# laser_show_core.net
KiCad netlist of a schematic drawn in Altium Designer
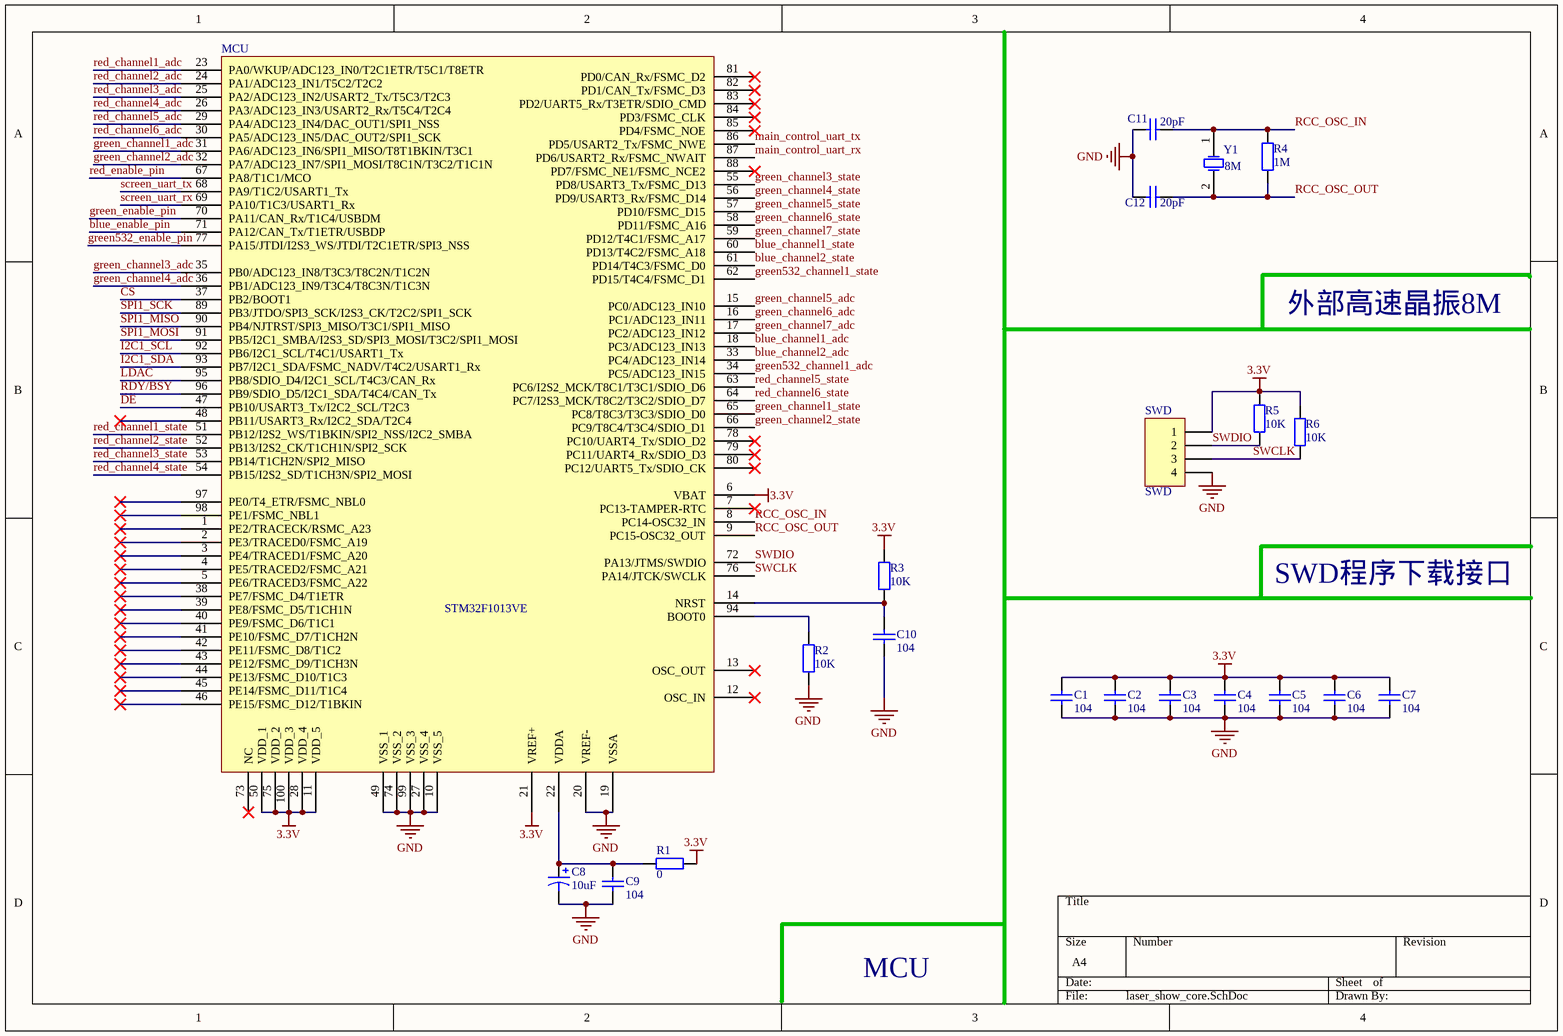
[diagram p0: laser_show_core.SchDoc]

(export (version "E")
  (design (tool "Eeschema 10.0.6"))
  (components
    (comp (ref "C1")
      (value "104")
      (footprint "0603C")
      (description "capacitance")
      (libsource (lib "RobotSCHLibrary") (part "CAP"))
    )
    (comp (ref "C2")
      (value "104")
      (footprint "0603C")
      (description "capacitance")
      (libsource (lib "RobotSCHLibrary") (part "CAP"))
    )
    (comp (ref "C3")
      (value "104")
      (footprint "0603C")
      (description "capacitance")
      (libsource (lib "RobotSCHLibrary") (part "CAP"))
    )
    (comp (ref "C4")
      (value "104")
      (footprint "0603C")
      (description "capacitance")
      (libsource (lib "RobotSCHLibrary") (part "CAP"))
    )
    (comp (ref "C5")
      (value "104")
      (footprint "0603C")
      (description "capacitance")
      (libsource (lib "RobotSCHLibrary") (part "CAP"))
    )
    (comp (ref "C6")
      (value "104")
      (footprint "0603C")
      (description "capacitance")
      (libsource (lib "RobotSCHLibrary") (part "CAP"))
    )
    (comp (ref "C7")
      (value "104")
      (footprint "0603C")
      (description "capacitance")
      (libsource (lib "RobotSCHLibrary") (part "CAP"))
    )
    (comp (ref "C8")
      (value "10uF")
      (footprint "0805CAP_POL")
      (description "Cap polar")
      (libsource (lib "RobotSCHLibrary") (part "CAP_Polar"))
    )
    (comp (ref "C9")
      (value "104")
      (footprint "0805C")
      (description "capacitance")
      (libsource (lib "RobotSCHLibrary") (part "CAP"))
    )
    (comp (ref "C10")
      (value "104")
      (footprint "0805C")
      (description "capacitance")
      (libsource (lib "RobotSCHLibrary") (part "CAP"))
    )
    (comp (ref "C11")
      (value "20pF")
      (footprint "0805C")
      (description "capacitance")
      (libsource (lib "RobotSCHLibrary") (part "CAP"))
    )
    (comp (ref "C12")
      (value "20pF")
      (footprint "0805C")
      (description "capacitance")
      (libsource (lib "RobotSCHLibrary") (part "CAP"))
    )
    (comp (ref "MCU")
      (value "STM32F1013VE")
      (footprint "LQFP100_L")
      (description "STM32F1013VET6")
      (libsource (lib "RobotSCHLibrary") (part "STM32F103VET6"))
    )
    (comp (ref "R1")
      (value "0")
      (footprint "0603R")
      (description "resistor")
      (libsource (lib "") (part "RES_2"))
    )
    (comp (ref "R2")
      (value "10K")
      (footprint "0603R")
      (description "resistor")
      (libsource (lib "RobotSCHLibrary") (part "RES"))
    )
    (comp (ref "R3")
      (value "10K")
      (footprint "0805R")
      (description "resistor")
      (libsource (lib "RobotSCHLibrary") (part "RES"))
    )
    (comp (ref "R4")
      (value "1M")
      (footprint "0805R")
      (description "resistor")
      (libsource (lib "") (part "RES_1"))
    )
    (comp (ref "R5")
      (value "10K")
      (footprint "0805R")
      (description "resistor")
      (libsource (lib "RobotSCHLibrary") (part "RES"))
    )
    (comp (ref "R6")
      (value "10K")
      (footprint "0805R")
      (description "resistor")
      (libsource (lib "RobotSCHLibrary") (part "RES"))
    )
    (comp (ref "SWD")
      (value "SWD")
      (footprint "HDR1X4")
      (description "Header, 4-Pin")
      (fields (field (name "PUBLISHER") "Altium Limited"))
      (libsource (lib "Miscellaneous Connectors") (part "Header 4"))
    )
    (comp (ref "Y1")
      (value "8M")
      (footprint "XTAL1")
      (description "crystal")
      (libsource (lib "RobotSCHLibrary") (part "8M"))
    )
  )
  (nets
    (net (code "1") (name "/CS") (class "Default")
      (node (ref "MCU") (pin "37") (pinfunction "PB2/BOOT1_37") (pintype "passive"))
    )
    (net (code "2") (name "/DE") (class "Default")
      (node (ref "MCU") (pin "47") (pinfunction "PB10/USART3_Tx/I2C2_SCL/T2C3_47") (pintype "passive"))
    )
    (net (code "3") (name "/I2C1_SCL") (class "Default")
      (node (ref "MCU") (pin "92") (pinfunction "PB6/I2C1_SCL/T4C1/USART1_Tx_92") (pintype "passive"))
    )
    (net (code "4") (name "/I2C1_SDA") (class "Default")
      (node (ref "MCU") (pin "93") (pinfunction "PB7/I2C1_SDA/FSMC_NADV/T4C2/USART1_Rx_93") (pintype "passive"))
    )
    (net (code "5") (name "/RCC_OSC_IN") (class "Default")
      (node (ref "C11") (pin "1") (pinfunction "1_1") (pintype "passive"))
      (node (ref "MCU") (pin "8") (pinfunction "PC14-OSC32_IN_8") (pintype "passive"))
      (node (ref "R4") (pin "1") (pinfunction "1_1") (pintype "passive"))
      (node (ref "Y1") (pin "1") (pinfunction "OSC1_1") (pintype "passive"))
    )
    (net (code "6") (name "/RCC_OSC_OUT") (class "Default")
      (node (ref "C12") (pin "1") (pinfunction "1_1") (pintype "passive"))
      (node (ref "MCU") (pin "9") (pinfunction "PC15-OSC32_OUT_9") (pintype "passive"))
      (node (ref "R4") (pin "2") (pinfunction "2_2") (pintype "passive"))
      (node (ref "Y1") (pin "2") (pinfunction "OSC2_2") (pintype "passive"))
    )
    (net (code "7") (name "/RDY{slash}~{BSY}") (class "Default")
      (node (ref "MCU") (pin "96") (pinfunction "PB9/SDIO_D5/I2C1_SDA/T4C4/CAN_Tx_96") (pintype "passive"))
    )
    (net (code "8") (name "/SPI1_MISO") (class "Default")
      (node (ref "MCU") (pin "90") (pinfunction "PB4/NJTRST/SPI3_MISO/T3C1/SPI1_MISO_90") (pintype "passive"))
    )
    (net (code "9") (name "/SPI1_MOSI") (class "Default")
      (node (ref "MCU") (pin "91") (pinfunction "PB5/I2C1_SMBA/I2S3_SD/SPI3_MOSI/T3C2/SPI1_MOSI_91") (pintype "passive"))
    )
    (net (code "10") (name "/SPI1_SCK") (class "Default")
      (node (ref "MCU") (pin "89") (pinfunction "PB3/JTDO/SPI3_SCK/I2S3_CK/T2C2/SPI1_SCK_89") (pintype "passive"))
    )
    (net (code "11") (name "/SWCLK") (class "Default")
      (node (ref "MCU") (pin "76") (pinfunction "PA14/JTCK/SWCLK_76") (pintype "passive"))
      (node (ref "R6") (pin "1") (pinfunction "1_1") (pintype "passive"))
      (node (ref "SWD") (pin "3") (pinfunction "3_3") (pintype "passive"))
    )
    (net (code "12") (name "/SWDIO") (class "Default")
      (node (ref "MCU") (pin "72") (pinfunction "PA13/JTMS/SWDIO_72") (pintype "passive"))
      (node (ref "R5") (pin "1") (pinfunction "1_1") (pintype "passive"))
      (node (ref "SWD") (pin "2") (pinfunction "2_2") (pintype "passive"))
    )
    (net (code "13") (name "/blue_channel1_adc") (class "Default")
      (node (ref "MCU") (pin "18") (pinfunction "PC3/ADC123_IN13_18") (pintype "passive"))
    )
    (net (code "14") (name "/blue_channel1_state") (class "Default")
      (node (ref "MCU") (pin "60") (pinfunction "PD13/T4C2/FSMC_A18_60") (pintype "passive"))
    )
    (net (code "15") (name "/blue_channel2_adc") (class "Default")
      (node (ref "MCU") (pin "33") (pinfunction "PC4/ADC123_IN14_33") (pintype "passive"))
    )
    (net (code "16") (name "/blue_channel2_state") (class "Default")
      (node (ref "MCU") (pin "61") (pinfunction "PD14/T4C3/FSMC_D0_61") (pintype "passive"))
    )
    (net (code "17") (name "/blue_enable_pin") (class "Default")
      (node (ref "MCU") (pin "71") (pinfunction "PA12/CAN_Tx/T1ETR/USBDP_71") (pintype "passive"))
    )
    (net (code "18") (name "/green532_channel1_adc") (class "Default")
      (node (ref "MCU") (pin "34") (pinfunction "PC5/ADC123_IN15_34") (pintype "passive"))
    )
    (net (code "19") (name "/green532_channel1_state") (class "Default")
      (node (ref "MCU") (pin "62") (pinfunction "PD15/T4C4/FSMC_D1_62") (pintype "passive"))
    )
    (net (code "20") (name "/green532_enable_pin") (class "Default")
      (node (ref "MCU") (pin "77") (pinfunction "PA15/JTDI/I2S3_WS/JTDI/T2C1ETR/SPI3_NSS_77") (pintype "passive"))
    )
    (net (code "21") (name "/green_channel1_adc") (class "Default")
      (node (ref "MCU") (pin "31") (pinfunction "PA6/ADC123_IN6/SPI1_MISO/T8T1BKIN/T3C1_31") (pintype "passive"))
    )
    (net (code "22") (name "/green_channel1_state") (class "Default")
      (node (ref "MCU") (pin "65") (pinfunction "PC8/T8C3/T3C3/SDIO_D0_65") (pintype "passive"))
    )
    (net (code "23") (name "/green_channel2_adc") (class "Default")
      (node (ref "MCU") (pin "32") (pinfunction "PA7/ADC123_IN7/SPI1_MOSI/T8C1N/T3C2/T1C1N_32") (pintype "passive"))
    )
    (net (code "24") (name "/green_channel2_state") (class "Default")
      (node (ref "MCU") (pin "66") (pinfunction "PC9/T8C4/T3C4/SDIO_D1_66") (pintype "passive"))
    )
    (net (code "25") (name "/green_channel3_adc") (class "Default")
      (node (ref "MCU") (pin "35") (pinfunction "PB0/ADC123_IN8/T3C3/T8C2N/T1C2N_35") (pintype "passive"))
    )
    (net (code "26") (name "/green_channel3_state") (class "Default")
      (node (ref "MCU") (pin "55") (pinfunction "PD8/USART3_Tx/FSMC_D13_55") (pintype "passive"))
    )
    (net (code "27") (name "/green_channel4_adc") (class "Default")
      (node (ref "MCU") (pin "36") (pinfunction "PB1/ADC123_IN9/T3C4/T8C3N/T1C3N_36") (pintype "passive"))
    )
    (net (code "28") (name "/green_channel4_state") (class "Default")
      (node (ref "MCU") (pin "56") (pinfunction "PD9/USART3_Rx/FSMC_D14_56") (pintype "passive"))
    )
    (net (code "29") (name "/green_channel5_adc") (class "Default")
      (node (ref "MCU") (pin "15") (pinfunction "PC0/ADC123_IN10_15") (pintype "passive"))
    )
    (net (code "30") (name "/green_channel5_state") (class "Default")
      (node (ref "MCU") (pin "57") (pinfunction "PD10/FSMC_D15_57") (pintype "passive"))
    )
    (net (code "31") (name "/green_channel6_adc") (class "Default")
      (node (ref "MCU") (pin "16") (pinfunction "PC1/ADC123_IN11_16") (pintype "passive"))
    )
    (net (code "32") (name "/green_channel6_state") (class "Default")
      (node (ref "MCU") (pin "58") (pinfunction "PD11/FSMC_A16_58") (pintype "passive"))
    )
    (net (code "33") (name "/green_channel7_adc") (class "Default")
      (node (ref "MCU") (pin "17") (pinfunction "PC2/ADC123_IN12_17") (pintype "passive"))
    )
    (net (code "34") (name "/green_channel7_state") (class "Default")
      (node (ref "MCU") (pin "59") (pinfunction "PD12/T4C1/FSMC_A17_59") (pintype "passive"))
    )
    (net (code "35") (name "/green_enable_pin") (class "Default")
      (node (ref "MCU") (pin "70") (pinfunction "PA11/CAN_Rx/T1C4/USBDM_70") (pintype "passive"))
    )
    (net (code "36") (name "/main_control_uart_rx") (class "Default")
      (node (ref "MCU") (pin "87") (pinfunction "PD6/USART2_Rx/FSMC_NWAIT_87") (pintype "passive"))
    )
    (net (code "37") (name "/main_control_uart_tx") (class "Default")
      (node (ref "MCU") (pin "86") (pinfunction "PD5/USART2_Tx/FSMC_NWE_86") (pintype "passive"))
    )
    (net (code "38") (name "/red_channel1_adc") (class "Default")
      (node (ref "MCU") (pin "23") (pinfunction "PA0/WKUP/ADC123_IN0/T2C1ETR/T5C1/T8ETR_23") (pintype "passive"))
    )
    (net (code "39") (name "/red_channel1_state") (class "Default")
      (node (ref "MCU") (pin "51") (pinfunction "PB12/I2S2_WS/T1BKIN/SPI2_NSS/I2C2_SMBA_51") (pintype "passive"))
    )
    (net (code "40") (name "/red_channel2_adc") (class "Default")
      (node (ref "MCU") (pin "24") (pinfunction "PA1/ADC123_IN1/T5C2/T2C2_24") (pintype "passive"))
    )
    (net (code "41") (name "/red_channel2_state") (class "Default")
      (node (ref "MCU") (pin "52") (pinfunction "PB13/I2S2_CK/T1CH1N/SPI2_SCK_52") (pintype "passive"))
    )
    (net (code "42") (name "/red_channel3_adc") (class "Default")
      (node (ref "MCU") (pin "25") (pinfunction "PA2/ADC123_IN2/USART2_Tx/T5C3/T2C3_25") (pintype "passive"))
    )
    (net (code "43") (name "/red_channel3_state") (class "Default")
      (node (ref "MCU") (pin "53") (pinfunction "PB14/T1CH2N/SPI2_MISO_53") (pintype "passive"))
    )
    (net (code "44") (name "/red_channel4_adc") (class "Default")
      (node (ref "MCU") (pin "26") (pinfunction "PA3/ADC123_IN3/USART2_Rx/T5C4/T2C4_26") (pintype "passive"))
    )
    (net (code "45") (name "/red_channel4_state") (class "Default")
      (node (ref "MCU") (pin "54") (pinfunction "PB15/I2S2_SD/T1CH3N/SPI2_MOSI_54") (pintype "passive"))
    )
    (net (code "46") (name "/red_channel5_adc") (class "Default")
      (node (ref "MCU") (pin "29") (pinfunction "PA4/ADC123_IN4/DAC_OUT1/SPI1_NSS_29") (pintype "passive"))
    )
    (net (code "47") (name "/red_channel5_state") (class "Default")
      (node (ref "MCU") (pin "63") (pinfunction "PC6/I2S2_MCK/T8C1/T3C1/SDIO_D6_63") (pintype "passive"))
    )
    (net (code "48") (name "/red_channel6_adc") (class "Default")
      (node (ref "MCU") (pin "30") (pinfunction "PA5/ADC123_IN5/DAC_OUT2/SPI1_SCK_30") (pintype "passive"))
    )
    (net (code "49") (name "/red_channel6_state") (class "Default")
      (node (ref "MCU") (pin "64") (pinfunction "PC7/I2S3_MCK/T8C2/T3C2/SDIO_D7_64") (pintype "passive"))
    )
    (net (code "50") (name "/red_enable_pin") (class "Default")
      (node (ref "MCU") (pin "67") (pinfunction "PA8/T1C1/MCO_67") (pintype "passive"))
    )
    (net (code "51") (name "/screen_uart_rx") (class "Default")
      (node (ref "MCU") (pin "69") (pinfunction "PA10/T1C3/USART1_Rx_69") (pintype "passive"))
    )
    (net (code "52") (name "/screen_uart_tx") (class "Default")
      (node (ref "MCU") (pin "68") (pinfunction "PA9/T1C2/USART1_Tx_68") (pintype "passive"))
    )
    (net (code "53") (name "/~{LDA}C") (class "Default")
      (node (ref "MCU") (pin "95") (pinfunction "PB8/SDIO_D4/I2C1_SCL/T4C3/CAN_Rx_95") (pintype "passive"))
    )
    (net (code "54") (name "3.3V") (class "Default")
      (node (ref "C1") (pin "2") (pinfunction "2_2") (pintype "passive"))
      (node (ref "C2") (pin "2") (pinfunction "2_2") (pintype "passive"))
      (node (ref "C3") (pin "2") (pinfunction "2_2") (pintype "passive"))
      (node (ref "C4") (pin "2") (pinfunction "2_2") (pintype "passive"))
      (node (ref "C5") (pin "2") (pinfunction "2_2") (pintype "passive"))
      (node (ref "C6") (pin "2") (pinfunction "2_2") (pintype "passive"))
      (node (ref "C7") (pin "2") (pinfunction "2_2") (pintype "passive"))
      (node (ref "MCU") (pin "100") (pinfunction "VDD_3_100") (pintype "passive"))
      (node (ref "MCU") (pin "11") (pinfunction "VDD_5_11") (pintype "passive"))
      (node (ref "MCU") (pin "21") (pinfunction "VREF+_21") (pintype "passive"))
      (node (ref "MCU") (pin "28") (pinfunction "VDD_4_28") (pintype "passive"))
      (node (ref "MCU") (pin "50") (pinfunction "VDD_1_50") (pintype "passive"))
      (node (ref "MCU") (pin "6") (pinfunction "VBAT_6") (pintype "passive"))
      (node (ref "MCU") (pin "75") (pinfunction "VDD_2_75") (pintype "passive"))
      (node (ref "R1") (pin "2") (pinfunction "2_2") (pintype "passive"))
      (node (ref "R3") (pin "2") (pinfunction "2_2") (pintype "passive"))
      (node (ref "R5") (pin "2") (pinfunction "2_2") (pintype "passive"))
      (node (ref "R6") (pin "2") (pinfunction "2_2") (pintype "passive"))
      (node (ref "SWD") (pin "1") (pinfunction "1_1") (pintype "passive"))
    )
    (net (code "55") (name "GND") (class "Default")
      (node (ref "C1") (pin "1") (pinfunction "1_1") (pintype "passive"))
      (node (ref "C10") (pin "1") (pinfunction "1_1") (pintype "passive"))
      (node (ref "C11") (pin "2") (pinfunction "2_2") (pintype "passive"))
      (node (ref "C12") (pin "2") (pinfunction "2_2") (pintype "passive"))
      (node (ref "C2") (pin "1") (pinfunction "1_1") (pintype "passive"))
      (node (ref "C3") (pin "1") (pinfunction "1_1") (pintype "passive"))
      (node (ref "C4") (pin "1") (pinfunction "1_1") (pintype "passive"))
      (node (ref "C5") (pin "1") (pinfunction "1_1") (pintype "passive"))
      (node (ref "C6") (pin "1") (pinfunction "1_1") (pintype "passive"))
      (node (ref "C7") (pin "1") (pinfunction "1_1") (pintype "passive"))
      (node (ref "C8") (pin "2") (pinfunction "2_2") (pintype "passive"))
      (node (ref "C9") (pin "1") (pinfunction "1_1") (pintype "passive"))
      (node (ref "MCU") (pin "10") (pinfunction "VSS_5_10") (pintype "passive"))
      (node (ref "MCU") (pin "19") (pinfunction "VSSA_19") (pintype "passive"))
      (node (ref "MCU") (pin "20") (pinfunction "VREF-_20") (pintype "passive"))
      (node (ref "MCU") (pin "27") (pinfunction "VSS_4_27") (pintype "passive"))
      (node (ref "MCU") (pin "49") (pinfunction "VSS_1_49") (pintype "passive"))
      (node (ref "MCU") (pin "74") (pinfunction "VSS_2_74") (pintype "passive"))
      (node (ref "MCU") (pin "99") (pinfunction "VSS_3_99") (pintype "passive"))
      (node (ref "R2") (pin "1") (pinfunction "1_1") (pintype "passive"))
      (node (ref "SWD") (pin "4") (pinfunction "4_4") (pintype "passive"))
    )
    (net (code "56") (name "Net-(MCU-BOOT0)") (class "Default")
      (node (ref "MCU") (pin "94") (pinfunction "BOOT0_94") (pintype "passive"))
      (node (ref "R2") (pin "2") (pinfunction "2_2") (pintype "passive"))
    )
    (net (code "57") (name "Net-(MCU-NRST)") (class "Default")
      (node (ref "C10") (pin "2") (pinfunction "2_2") (pintype "passive"))
      (node (ref "MCU") (pin "14") (pinfunction "NRST_14") (pintype "passive"))
      (node (ref "R3") (pin "1") (pinfunction "1_1") (pintype "passive"))
    )
    (net (code "58") (name "Net-(MCU-VDDA)") (class "Default")
      (node (ref "C8") (pin "1") (pinfunction "1_1") (pintype "passive"))
      (node (ref "C9") (pin "2") (pinfunction "2_2") (pintype "passive"))
      (node (ref "MCU") (pin "22") (pinfunction "VDDA_22") (pintype "passive"))
      (node (ref "R1") (pin "1") (pinfunction "1_1") (pintype "passive"))
    )
    (net (code "59") (name "unconnected-(MCU-NC-Pad73)") (class "Default")
      (node (ref "MCU") (pin "73") (pinfunction "NC_73") (pintype "passive+no_connect"))
    )
    (net (code "60") (name "unconnected-(MCU-OSC_IN-Pad12)") (class "Default")
      (node (ref "MCU") (pin "12") (pinfunction "OSC_IN_12") (pintype "passive+no_connect"))
    )
    (net (code "61") (name "unconnected-(MCU-OSC_OUT-Pad13)") (class "Default")
      (node (ref "MCU") (pin "13") (pinfunction "OSC_OUT_13") (pintype "passive+no_connect"))
    )
    (net (code "62") (name "unconnected-(MCU-PB11{slash}USART3_Rx{slash}I2C2_SDA{slash}T2C4-Pad48)") (class "Default")
      (node (ref "MCU") (pin "48") (pinfunction "PB11/USART3_Rx/I2C2_SDA/T2C4_48") (pintype "passive+no_connect"))
    )
    (net (code "63") (name "unconnected-(MCU-PC10{slash}UART4_Tx{slash}SDIO_D2-Pad78)") (class "Default")
      (node (ref "MCU") (pin "78") (pinfunction "PC10/UART4_Tx/SDIO_D2_78") (pintype "passive+no_connect"))
    )
    (net (code "64") (name "unconnected-(MCU-PC11{slash}UART4_Rx{slash}SDIO_D3-Pad79)") (class "Default")
      (node (ref "MCU") (pin "79") (pinfunction "PC11/UART4_Rx/SDIO_D3_79") (pintype "passive+no_connect"))
    )
    (net (code "65") (name "unconnected-(MCU-PC12{slash}UART5_Tx{slash}SDIO_CK-Pad80)") (class "Default")
      (node (ref "MCU") (pin "80") (pinfunction "PC12/UART5_Tx/SDIO_CK_80") (pintype "passive+no_connect"))
    )
    (net (code "66") (name "unconnected-(MCU-PC13-TAMPER-RTC-Pad7)") (class "Default")
      (node (ref "MCU") (pin "7") (pinfunction "PC13-TAMPER-RTC_7") (pintype "passive+no_connect"))
    )
    (net (code "67") (name "unconnected-(MCU-PD0{slash}CAN_Rx{slash}FSMC_D2-Pad81)") (class "Default")
      (node (ref "MCU") (pin "81") (pinfunction "PD0/CAN_Rx/FSMC_D2_81") (pintype "passive+no_connect"))
    )
    (net (code "68") (name "unconnected-(MCU-PD1{slash}CAN_Tx{slash}FSMC_D3-Pad82)") (class "Default")
      (node (ref "MCU") (pin "82") (pinfunction "PD1/CAN_Tx/FSMC_D3_82") (pintype "passive+no_connect"))
    )
    (net (code "69") (name "unconnected-(MCU-PD2{slash}UART5_Rx{slash}T3ETR{slash}SDIO_CMD-Pad83)") (class "Default")
      (node (ref "MCU") (pin "83") (pinfunction "PD2/UART5_Rx/T3ETR/SDIO_CMD_83") (pintype "passive+no_connect"))
    )
    (net (code "70") (name "unconnected-(MCU-PD3{slash}FSMC_CLK-Pad84)") (class "Default")
      (node (ref "MCU") (pin "84") (pinfunction "PD3/FSMC_CLK_84") (pintype "passive+no_connect"))
    )
    (net (code "71") (name "unconnected-(MCU-PD4{slash}FSMC_NOE-Pad85)") (class "Default")
      (node (ref "MCU") (pin "85") (pinfunction "PD4/FSMC_NOE_85") (pintype "passive+no_connect"))
    )
    (net (code "72") (name "unconnected-(MCU-PD7{slash}FSMC_NE1{slash}FSMC_NCE2-Pad88)") (class "Default")
      (node (ref "MCU") (pin "88") (pinfunction "PD7/FSMC_NE1/FSMC_NCE2_88") (pintype "passive+no_connect"))
    )
    (net (code "73") (name "unconnected-(MCU-PE0{slash}T4_ETR{slash}FSMC_NBL0-Pad97)") (class "Default")
      (node (ref "MCU") (pin "97") (pinfunction "PE0/T4_ETR/FSMC_NBL0_97") (pintype "passive+no_connect"))
    )
    (net (code "74") (name "unconnected-(MCU-PE1{slash}FSMC_NBL1-Pad98)") (class "Default")
      (node (ref "MCU") (pin "98") (pinfunction "PE1/FSMC_NBL1_98") (pintype "passive+no_connect"))
    )
    (net (code "75") (name "unconnected-(MCU-PE2{slash}TRACECK{slash}RSMC_A23-Pad1)") (class "Default")
      (node (ref "MCU") (pin "1") (pinfunction "PE2/TRACECK/RSMC_A23_1") (pintype "passive+no_connect"))
    )
    (net (code "76") (name "unconnected-(MCU-PE3{slash}TRACED0{slash}FSMC_A19-Pad2)") (class "Default")
      (node (ref "MCU") (pin "2") (pinfunction "PE3/TRACED0/FSMC_A19_2") (pintype "passive+no_connect"))
    )
    (net (code "77") (name "unconnected-(MCU-PE4{slash}TRACED1{slash}FSMC_A20-Pad3)") (class "Default")
      (node (ref "MCU") (pin "3") (pinfunction "PE4/TRACED1/FSMC_A20_3") (pintype "passive+no_connect"))
    )
    (net (code "78") (name "unconnected-(MCU-PE5{slash}TRACED2{slash}FSMC_A21-Pad4)") (class "Default")
      (node (ref "MCU") (pin "4") (pinfunction "PE5/TRACED2/FSMC_A21_4") (pintype "passive+no_connect"))
    )
    (net (code "79") (name "unconnected-(MCU-PE6{slash}TRACED3{slash}FSMC_A22-Pad5)") (class "Default")
      (node (ref "MCU") (pin "5") (pinfunction "PE6/TRACED3/FSMC_A22_5") (pintype "passive+no_connect"))
    )
    (net (code "80") (name "unconnected-(MCU-PE7{slash}FSMC_D4{slash}T1ETR-Pad38)") (class "Default")
      (node (ref "MCU") (pin "38") (pinfunction "PE7/FSMC_D4/T1ETR_38") (pintype "passive+no_connect"))
    )
    (net (code "81") (name "unconnected-(MCU-PE8{slash}FSMC_D5{slash}T1CH1N-Pad39)") (class "Default")
      (node (ref "MCU") (pin "39") (pinfunction "PE8/FSMC_D5/T1CH1N_39") (pintype "passive+no_connect"))
    )
    (net (code "82") (name "unconnected-(MCU-PE9{slash}FSMC_D6{slash}T1C1-Pad40)") (class "Default")
      (node (ref "MCU") (pin "40") (pinfunction "PE9/FSMC_D6/T1C1_40") (pintype "passive+no_connect"))
    )
    (net (code "83") (name "unconnected-(MCU-PE10{slash}FSMC_D7{slash}T1CH2N-Pad41)") (class "Default")
      (node (ref "MCU") (pin "41") (pinfunction "PE10/FSMC_D7/T1CH2N_41") (pintype "passive+no_connect"))
    )
    (net (code "84") (name "unconnected-(MCU-PE11{slash}FSMC_D8{slash}T1C2-Pad42)") (class "Default")
      (node (ref "MCU") (pin "42") (pinfunction "PE11/FSMC_D8/T1C2_42") (pintype "passive+no_connect"))
    )
    (net (code "85") (name "unconnected-(MCU-PE12{slash}FSMC_D9{slash}T1CH3N-Pad43)") (class "Default")
      (node (ref "MCU") (pin "43") (pinfunction "PE12/FSMC_D9/T1CH3N_43") (pintype "passive+no_connect"))
    )
    (net (code "86") (name "unconnected-(MCU-PE13{slash}FSMC_D10{slash}T1C3-Pad44)") (class "Default")
      (node (ref "MCU") (pin "44") (pinfunction "PE13/FSMC_D10/T1C3_44") (pintype "passive+no_connect"))
    )
    (net (code "87") (name "unconnected-(MCU-PE14{slash}FSMC_D11{slash}T1C4-Pad45)") (class "Default")
      (node (ref "MCU") (pin "45") (pinfunction "PE14/FSMC_D11/T1C4_45") (pintype "passive+no_connect"))
    )
    (net (code "88") (name "unconnected-(MCU-PE15{slash}FSMC_D12{slash}T1BKIN-Pad46)") (class "Default")
      (node (ref "MCU") (pin "46") (pinfunction "PE15/FSMC_D12/T1BKIN_46") (pintype "passive+no_connect"))
    )
  )
)
